# mp3412-boost-driver-mk-1_0.net
KiCad netlist of a schematic drawn in EAGLE
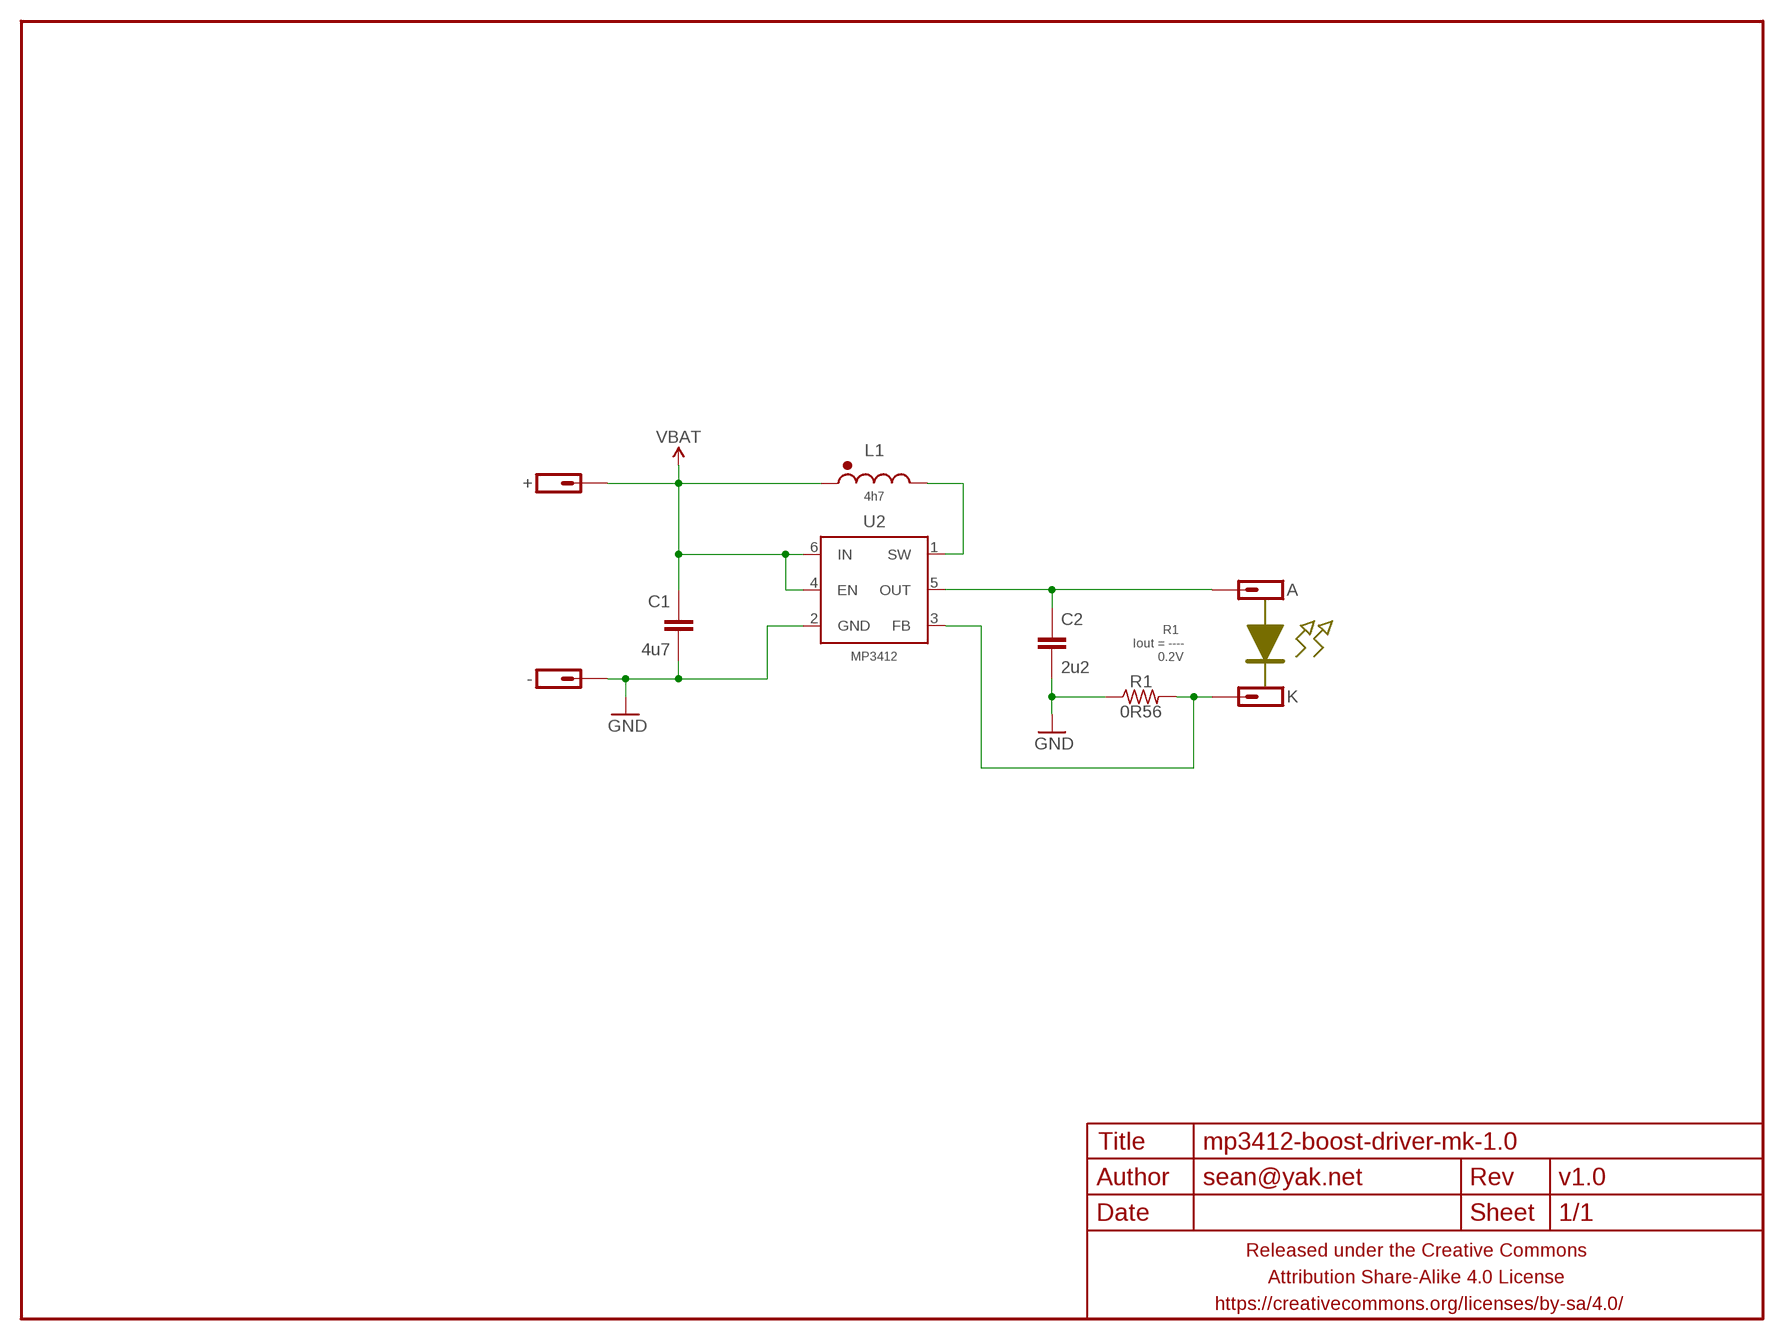
[diagram p0: schematic, sheet 1]

(export (version "E")
  (design (tool "Eeschema 10.0.6"))
  (components
    (comp (ref "+")
      (value "M01NOT-A-VIA-NOPE")
      (footprint "eagle-import:1X01_NOSILK_NOSTOP")
      (libsource (lib "eagle-import") (part "M01NOT-A-VIA-NOPE"))
    )
    (comp (ref "-")
      (value "M01NOT-A-VIA-NOPE")
      (footprint "eagle-import:1X01_NOSILK_NOSTOP")
      (libsource (lib "eagle-import") (part "M01NOT-A-VIA-NOPE"))
    )
    (comp (ref "A")
      (value "M01PTH-1MM-CIR-NS")
      (footprint "eagle-import:1X01-1MM-CIR-NS")
      (libsource (lib "eagle-import") (part "M01PTH-1MM-CIR-NS"))
    )
    (comp (ref "C1")
      (value "4u7")
      (footprint "eagle-import:C0603-TIGHTER")
      (libsource (lib "eagle-import") (part "CAPACITOR-CERAMICC0603-TIGHTER"))
    )
    (comp (ref "C2")
      (value "2u2")
      (footprint "eagle-import:C0603-TIGHTER")
      (libsource (lib "eagle-import") (part "CAPACITOR-CERAMICC0603-TIGHTER"))
    )
    (comp (ref "FRAME1")
      (value "FRAME-LETTERNO_PACKAGE")
      (footprint "eagle-import:DUMMY")
      (fields (field (name "DESIGNER") "sean@yak.net") (field (name "VERSION") "v1.0"))
      (libsource (lib "eagle-import") (part "FRAME-LETTERNO_PACKAGE"))
    )
    (comp (ref "K")
      (value "M01PTH-1MM-CIR-NS")
      (footprint "eagle-import:1X01-1MM-CIR-NS")
      (libsource (lib "eagle-import") (part "M01PTH-1MM-CIR-NS"))
    )
    (comp (ref "L1")
      (value "4h7")
      (footprint "eagle-import:EPL2014")
      (libsource (lib "eagle-import") (part "INDUCTOREPL2014"))
    )
    (comp (ref "R1")
      (value "0R56")
      (footprint "eagle-import:R0603-TIGHTER")
      (libsource (lib "eagle-import") (part "RESISTORR0603-TIGHTER"))
    )
    (comp (ref "U2")
      (value "MP3412")
      (footprint "eagle-import:TSOT-23-6")
      (libsource (lib "eagle-import") (part "MP3412"))
    )
  )
  (nets
    (net (code "1") (name "GND") (class "Default")
      (node (ref "-") (pin "P$1") (pinfunction "1_P$1") (pintype "passive"))
      (node (ref "C1") (pin "2") (pinfunction "2_2") (pintype "passive"))
      (node (ref "C2") (pin "2") (pinfunction "2_2") (pintype "passive"))
      (node (ref "R1") (pin "1") (pinfunction "1_1") (pintype "passive"))
      (node (ref "U2") (pin "2") (pinfunction "GND_2") (pintype "bidirectional"))
    )
    (net (code "2") (name "Net-(L1-2)") (class "Default")
      (node (ref "L1") (pin "P$2") (pinfunction "2_P$2") (pintype "passive"))
      (node (ref "U2") (pin "1") (pinfunction "SW_1") (pintype "bidirectional"))
    )
    (net (code "3") (name "Net-(U2-FB)") (class "Default")
      (node (ref "K") (pin "1") (pinfunction "1_1") (pintype "passive"))
      (node (ref "R1") (pin "2") (pinfunction "2_2") (pintype "passive"))
      (node (ref "U2") (pin "3") (pinfunction "FB_3") (pintype "bidirectional"))
    )
    (net (code "4") (name "Net-(U2-OUT)") (class "Default")
      (node (ref "A") (pin "1") (pinfunction "1_1") (pintype "passive"))
      (node (ref "C2") (pin "1") (pinfunction "1_1") (pintype "passive"))
      (node (ref "U2") (pin "5") (pinfunction "OUT_5") (pintype "bidirectional"))
    )
    (net (code "5") (name "VBAT") (class "Default")
      (node (ref "+") (pin "P$1") (pinfunction "1_P$1") (pintype "passive"))
      (node (ref "C1") (pin "1") (pinfunction "1_1") (pintype "passive"))
      (node (ref "L1") (pin "P$1") (pinfunction "1_P$1") (pintype "passive"))
      (node (ref "U2") (pin "4") (pinfunction "EN_4") (pintype "bidirectional"))
      (node (ref "U2") (pin "6") (pinfunction "IN_6") (pintype "bidirectional"))
    )
  )
)
